# Schema.net
KiCad netlist of a schematic drawn in Altium Designer
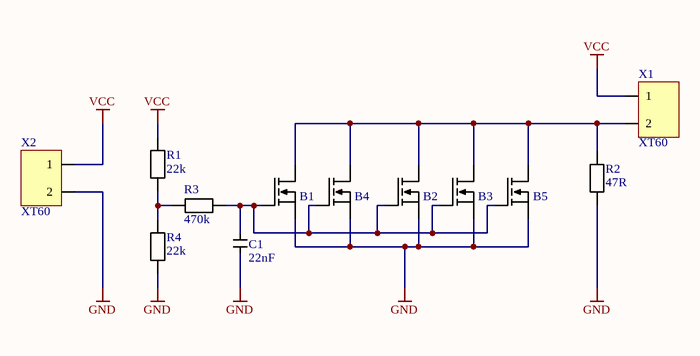
[diagram p0: Schema.SchDoc]

(export (version "E")
  (design (tool "Eeschema 10.0.6"))
  (components
    (comp (ref "B1")
      (value "N Kanal FET")
      (footprint "GeneralPCBLibrary:PowerPak SO-8")
      (libsource (lib "GeneralSchemaLibrary") (part "N Kanal FET"))
    )
    (comp (ref "B2")
      (value "N Kanal FET")
      (footprint "GeneralPCBLibrary:PowerPak SO-8")
      (libsource (lib "GeneralSchemaLibrary") (part "N Kanal FET"))
    )
    (comp (ref "B3")
      (value "N Kanal FET")
      (footprint "GeneralPCBLibrary:PowerPak SO-8")
      (libsource (lib "GeneralSchemaLibrary") (part "N Kanal FET"))
    )
    (comp (ref "B4")
      (value "N Kanal FET")
      (footprint "GeneralPCBLibrary:PowerPak SO-8")
      (libsource (lib "GeneralSchemaLibrary") (part "N Kanal FET"))
    )
    (comp (ref "B5")
      (value "N Kanal FET")
      (footprint "GeneralPCBLibrary:PowerPak SO-8")
      (libsource (lib "GeneralSchemaLibrary") (part "N Kanal FET"))
    )
    (comp (ref "C1")
      (value "22nF")
      (footprint "GeneralPCBLibrary:CAP CER 0805 H")
      (fields (field (name "Comment") "Capacitor 0805"))
      (libsource (lib "GeneralSchemaLibrary") (part "Capacitor 0805"))
    )
    (comp (ref "R1")
      (value "22k")
      (footprint "GeneralPCBLibrary:RES 0805 H")
      (fields (field (name "Comment") "Resistor 0805"))
      (libsource (lib "GeneralSchemaLibrary") (part "Resistor 0805"))
    )
    (comp (ref "R2")
      (value "47R")
      (footprint "GeneralPCBLibrary:DPAK Schottky")
      (fields (field (name "Comment") "Resistor 2512"))
      (libsource (lib "GeneralSchemaLibrary") (part "Resistor 2512"))
    )
    (comp (ref "R3")
      (value "470k")
      (footprint "GeneralPCBLibrary:RES 0805 H")
      (fields (field (name "Comment") "Resistor 0805"))
      (libsource (lib "GeneralSchemaLibrary") (part "Resistor 0805"))
    )
    (comp (ref "R4")
      (value "22k")
      (footprint "GeneralPCBLibrary:RES 0805 H")
      (fields (field (name "Comment") "Resistor 0805"))
      (libsource (lib "GeneralSchemaLibrary") (part "Resistor 0805"))
    )
    (comp (ref "X1")
      (value "XT60")
      (footprint "GeneralPCBLibrary:XT60_THT Male")
      (libsource (lib "GeneralSchemaLibrary") (part "XT60"))
    )
    (comp (ref "X2")
      (value "XT60")
      (footprint "GeneralPCBLibrary:XT60_THT Male")
      (libsource (lib "") (part "XT60_1"))
    )
  )
  (nets
    (net (code "1") (name "GND") (class "Default")
      (node (ref "B1") (pin "2") (pinfunction "Source_2") (pintype "passive"))
      (node (ref "B2") (pin "2") (pinfunction "Source_2") (pintype "passive"))
      (node (ref "B3") (pin "2") (pinfunction "Source_2") (pintype "passive"))
      (node (ref "B4") (pin "2") (pinfunction "Source_2") (pintype "passive"))
      (node (ref "B5") (pin "2") (pinfunction "Source_2") (pintype "passive"))
      (node (ref "C1") (pin "1") (pinfunction "1_1") (pintype "passive"))
      (node (ref "R2") (pin "1") (pinfunction "1_1") (pintype "passive"))
      (node (ref "R4") (pin "2") (pinfunction "2_2") (pintype "passive"))
      (node (ref "X2") (pin "2") (pinfunction "2_2") (pintype "passive"))
    )
    (net (code "2") (name "Net-(B1-Drain)") (class "Default")
      (node (ref "B1") (pin "3") (pinfunction "Drain_3") (pintype "passive"))
      (node (ref "B2") (pin "3") (pinfunction "Drain_3") (pintype "passive"))
      (node (ref "B3") (pin "3") (pinfunction "Drain_3") (pintype "passive"))
      (node (ref "B4") (pin "3") (pinfunction "Drain_3") (pintype "passive"))
      (node (ref "B5") (pin "3") (pinfunction "Drain_3") (pintype "passive"))
      (node (ref "R2") (pin "2") (pinfunction "2_2") (pintype "passive"))
      (node (ref "X1") (pin "2") (pinfunction "2_2") (pintype "passive"))
    )
    (net (code "3") (name "Net-(B1-Gate)") (class "Default")
      (node (ref "B1") (pin "1") (pinfunction "Gate_1") (pintype "passive"))
      (node (ref "B2") (pin "1") (pinfunction "Gate_1") (pintype "passive"))
      (node (ref "B3") (pin "1") (pinfunction "Gate_1") (pintype "passive"))
      (node (ref "B4") (pin "1") (pinfunction "Gate_1") (pintype "passive"))
      (node (ref "B5") (pin "1") (pinfunction "Gate_1") (pintype "passive"))
      (node (ref "C1") (pin "2") (pinfunction "2_2") (pintype "passive"))
      (node (ref "R3") (pin "2") (pinfunction "2_2") (pintype "passive"))
    )
    (net (code "4") (name "Net-(R1-Pad2)") (class "Default")
      (node (ref "R1") (pin "2") (pinfunction "2_2") (pintype "passive"))
      (node (ref "R3") (pin "1") (pinfunction "1_1") (pintype "passive"))
      (node (ref "R4") (pin "1") (pinfunction "1_1") (pintype "passive"))
    )
    (net (code "5") (name "VCC") (class "Default")
      (node (ref "R1") (pin "1") (pinfunction "1_1") (pintype "passive"))
      (node (ref "X1") (pin "1") (pinfunction "1_1") (pintype "passive"))
      (node (ref "X2") (pin "1") (pinfunction "1_1") (pintype "passive"))
    )
  )
)
